# v1_1.net
KiCad netlist of a schematic drawn in Altium Designer
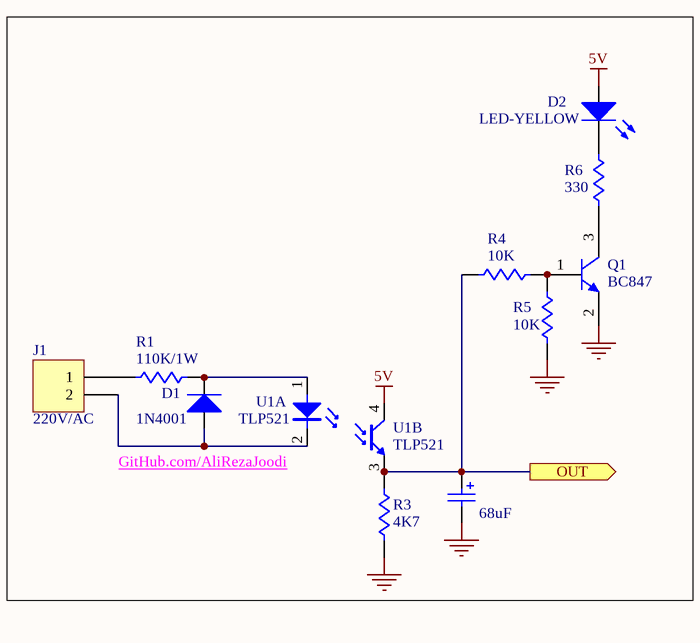
[diagram p0: v1.1.SchDoc]

(export (version "E")
  (design (tool "Eeschema 10.0.6"))
  (components
    (comp (ref "C1")
      (value "68uF")
      (footprint "Cap_D")
      (description "Polarized Capacitor (Radial)")
      (fields
        (field (name "MANUFACTURER") "Generic Components")
        (field (name "Comment") "CAP")
        (field (name "PUBLISHER") "Altium Limited")
      )
      (libsource (lib "Miscellaneous Devices") (part "Cap Pol1"))
    )
    (comp (ref "D1")
      (value "1N4001")
      (footprint "MELF-D3516-1406")
      (description "Default Diode")
      (fields (field (name "MANUFACTURER") "Generic Components") (field (name "PUBLISHER") "Altium Limited"))
      (libsource (lib "Miscellaneous Devices") (part "Diode"))
    )
    (comp (ref "D2")
      (value "LED-YELLOW")
      (footprint "0805_Diode")
      (description "Typical INFRARED GaAs LED")
      (fields (field (name "MANUFACTURER") "Generic Components") (field (name "PUBLISHER") "Altium Limited"))
      (libsource (lib "Miscellaneous Devices") (part "LED"))
    )
    (comp (ref "J1")
      (value "J9")
      (footprint "Fonics_2PIN_1")
      (description "Header, 2-Pin")
      (fields (field (name "PUBLISHER") "Altium Limited"))
      (libsource (lib "Miscellaneous Connectors") (part "Header 2"))
    )
    (comp (ref "Q1")
      (value "BC847")
      (footprint "SOT23-3N")
      (description "Silicon Bipolar Transistor")
      (libsource (lib "my Libraries") (part "BC847"))
    )
    (comp (ref "R1")
      (value "110K/1W")
      (footprint "0805")
      (description "Resistor")
      (fields (field (name "MANUFACTURER") "Generic Components") (field (name "PUBLISHER") "Altium Limited"))
      (libsource (lib "Miscellaneous Devices") (part "Res1"))
    )
    (comp (ref "R3")
      (value "4K7")
      (footprint "0805")
      (description "Resistor")
      (fields (field (name "MANUFACTURER") "Generic Components") (field (name "PUBLISHER") "Altium Limited"))
      (libsource (lib "Miscellaneous Devices") (part "Res1"))
    )
    (comp (ref "R4")
      (value "10K")
      (footprint "0805")
      (description "Resistor")
      (fields (field (name "MANUFACTURER") "Generic Components") (field (name "PUBLISHER") "Altium Limited"))
      (libsource (lib "Miscellaneous Devices") (part "Res1"))
    )
    (comp (ref "R5")
      (value "10K")
      (footprint "0805")
      (description "Resistor")
      (fields (field (name "MANUFACTURER") "Generic Components") (field (name "PUBLISHER") "Altium Limited"))
      (libsource (lib "Miscellaneous Devices") (part "Res1"))
    )
    (comp (ref "R6")
      (value "330")
      (footprint "0805")
      (description "Resistor")
      (fields (field (name "MANUFACTURER") "Generic Components") (field (name "PUBLISHER") "Altium Limited"))
      (libsource (lib "Miscellaneous Devices") (part "Res1"))
    )
    (comp (ref "U1")
      (value "TLP521")
      (footprint "SMD_4PIN")
      (fields (field (name "PUBLISHER") "Altium Limited"))
      (libsource (lib "my Libraries") (part "Optoisolator"))
    )
  )
  (nets
    (net (code "1") (name "/OUT") (class "Default")
      (node (ref "C1") (pin "1") (pinfunction "1_1") (pintype "passive"))
      (node (ref "R3") (pin "1") (pinfunction "1_1") (pintype "passive"))
      (node (ref "R4") (pin "1") (pinfunction "1_1") (pintype "passive"))
      (node (ref "U1") (pin "3") (pinfunction "E_3") (pintype "passive"))
    )
    (net (code "2") (name "5V") (class "Default")
      (node (ref "D2") (pin "1") (pinfunction "A_1") (pintype "passive"))
      (node (ref "U1") (pin "4") (pinfunction "C_4") (pintype "passive"))
    )
    (net (code "3") (name "GND") (class "Default")
      (node (ref "C1") (pin "2") (pinfunction "2_2") (pintype "passive"))
      (node (ref "Q1") (pin "2") (pinfunction "E_2") (pintype "passive"))
      (node (ref "R3") (pin "2") (pinfunction "2_2") (pintype "passive"))
      (node (ref "R5") (pin "1") (pinfunction "1_1") (pintype "passive"))
    )
    (net (code "4") (name "Net-(D1-A)") (class "Default")
      (node (ref "D1") (pin "1") (pinfunction "A_1") (pintype "passive"))
      (node (ref "J1") (pin "2") (pinfunction "2_2") (pintype "passive"))
      (node (ref "U1") (pin "2") (pinfunction "K_2") (pintype "power_in"))
    )
    (net (code "5") (name "Net-(D1-K)") (class "Default")
      (node (ref "D1") (pin "2") (pinfunction "K_2") (pintype "passive"))
      (node (ref "R1") (pin "2") (pinfunction "2_2") (pintype "passive"))
      (node (ref "U1") (pin "1") (pinfunction "A_1") (pintype "power_in"))
    )
    (net (code "6") (name "Net-(D2-K)") (class "Default")
      (node (ref "D2") (pin "2") (pinfunction "K_2") (pintype "passive"))
      (node (ref "R6") (pin "1") (pinfunction "1_1") (pintype "passive"))
    )
    (net (code "7") (name "Net-(J1-Pad1)") (class "Default")
      (node (ref "J1") (pin "1") (pinfunction "1_1") (pintype "passive"))
      (node (ref "R1") (pin "1") (pinfunction "1_1") (pintype "passive"))
    )
    (net (code "8") (name "Net-(Q1-B)") (class "Default")
      (node (ref "Q1") (pin "1") (pinfunction "B_1") (pintype "passive"))
      (node (ref "R4") (pin "2") (pinfunction "2_2") (pintype "passive"))
      (node (ref "R5") (pin "2") (pinfunction "2_2") (pintype "passive"))
    )
    (net (code "9") (name "Net-(Q1-C)") (class "Default")
      (node (ref "Q1") (pin "3") (pinfunction "C_3") (pintype "passive"))
      (node (ref "R6") (pin "2") (pinfunction "2_2") (pintype "passive"))
    )
  )
)
